# 612_jetracer_esp32s3_030011.net
KiCad netlist of a schematic drawn in EAGLE
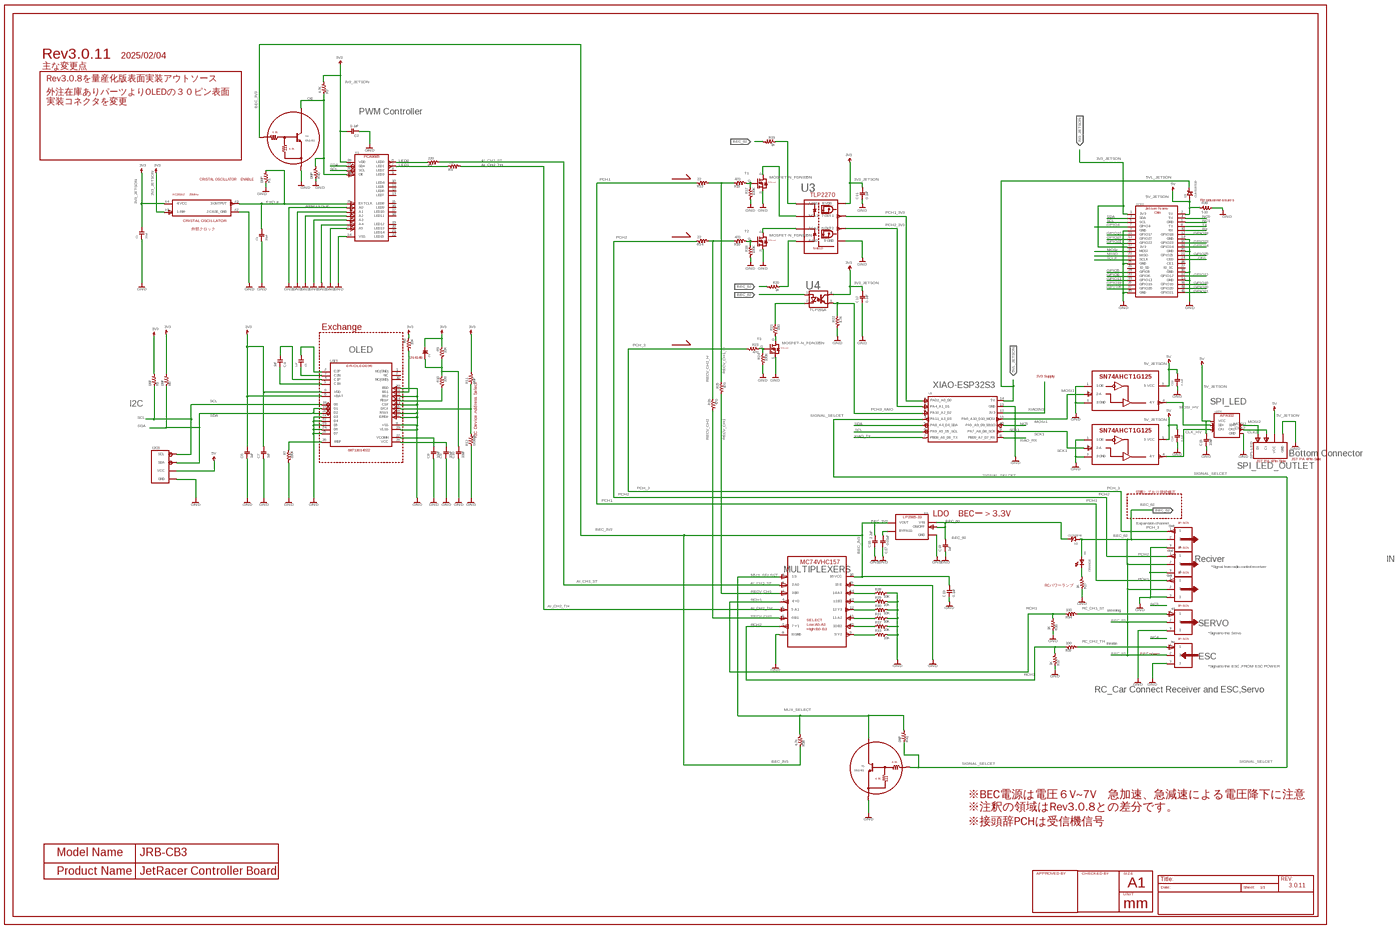
[diagram p0: schematic, sheet 1, overview]
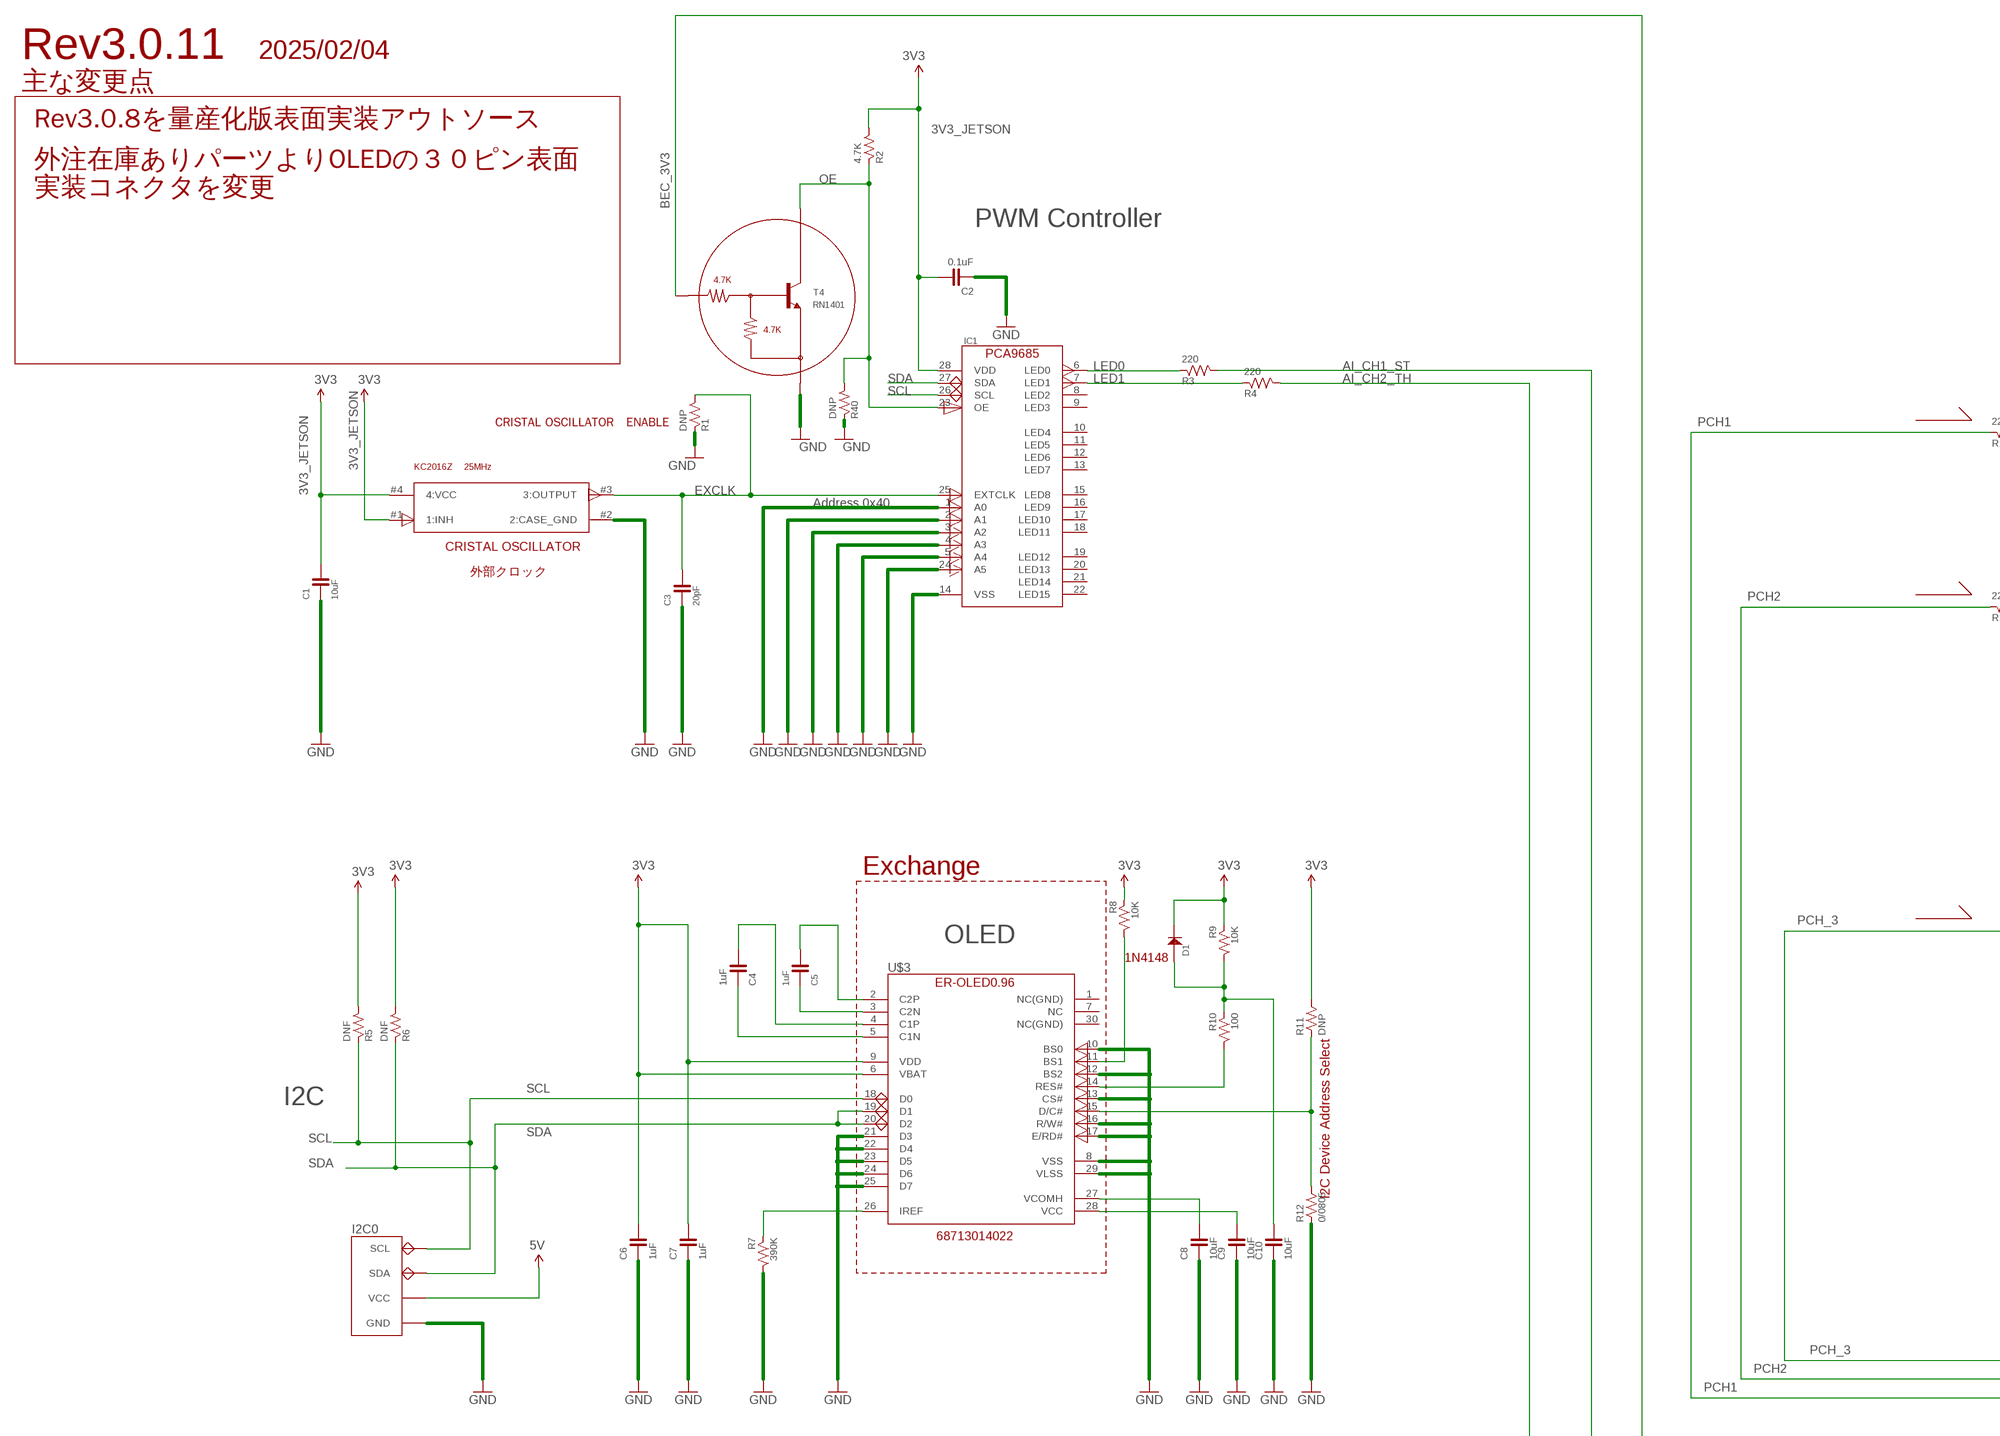
[diagram p1: schematic, sheet 1, part 1 of 4]
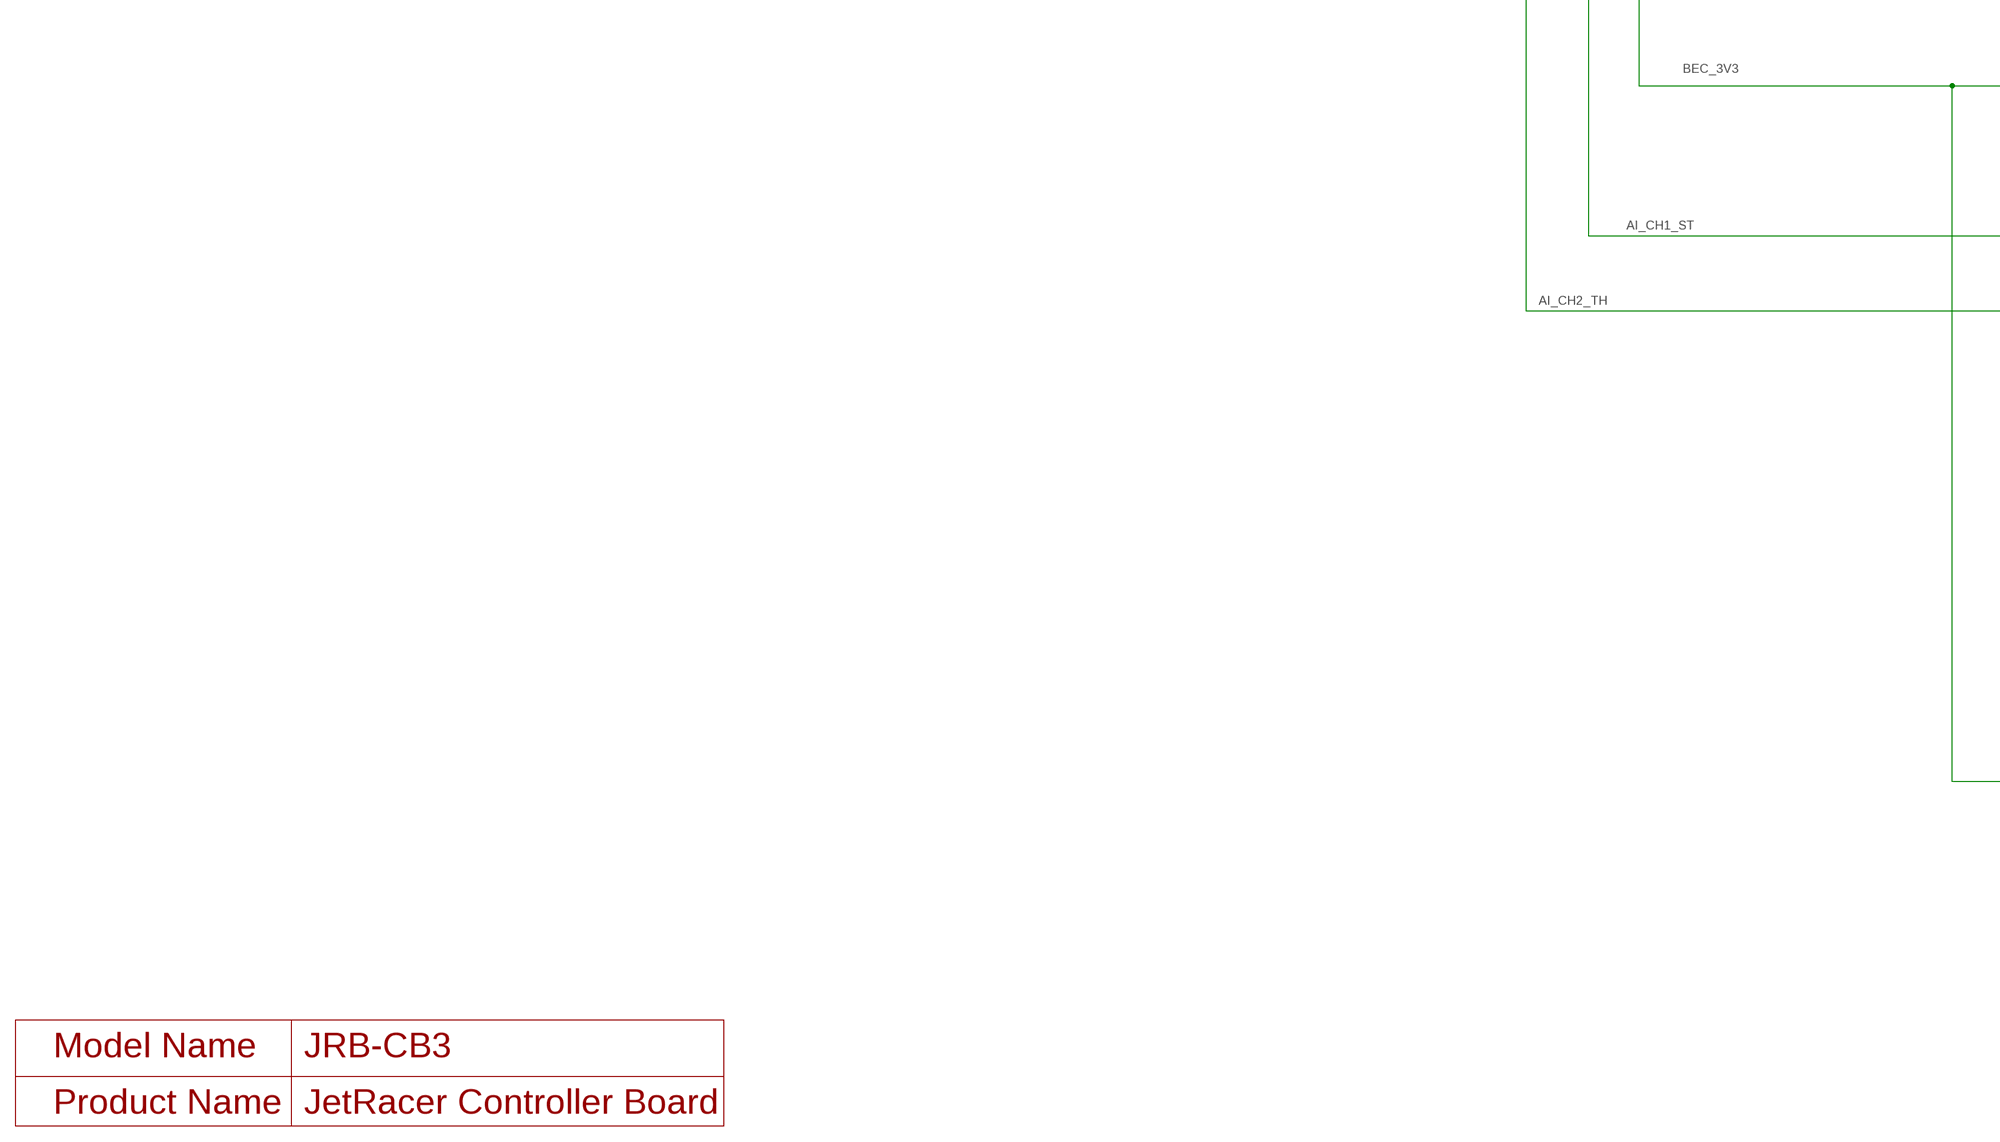
[diagram p2: schematic, sheet 1, part 2 of 4]
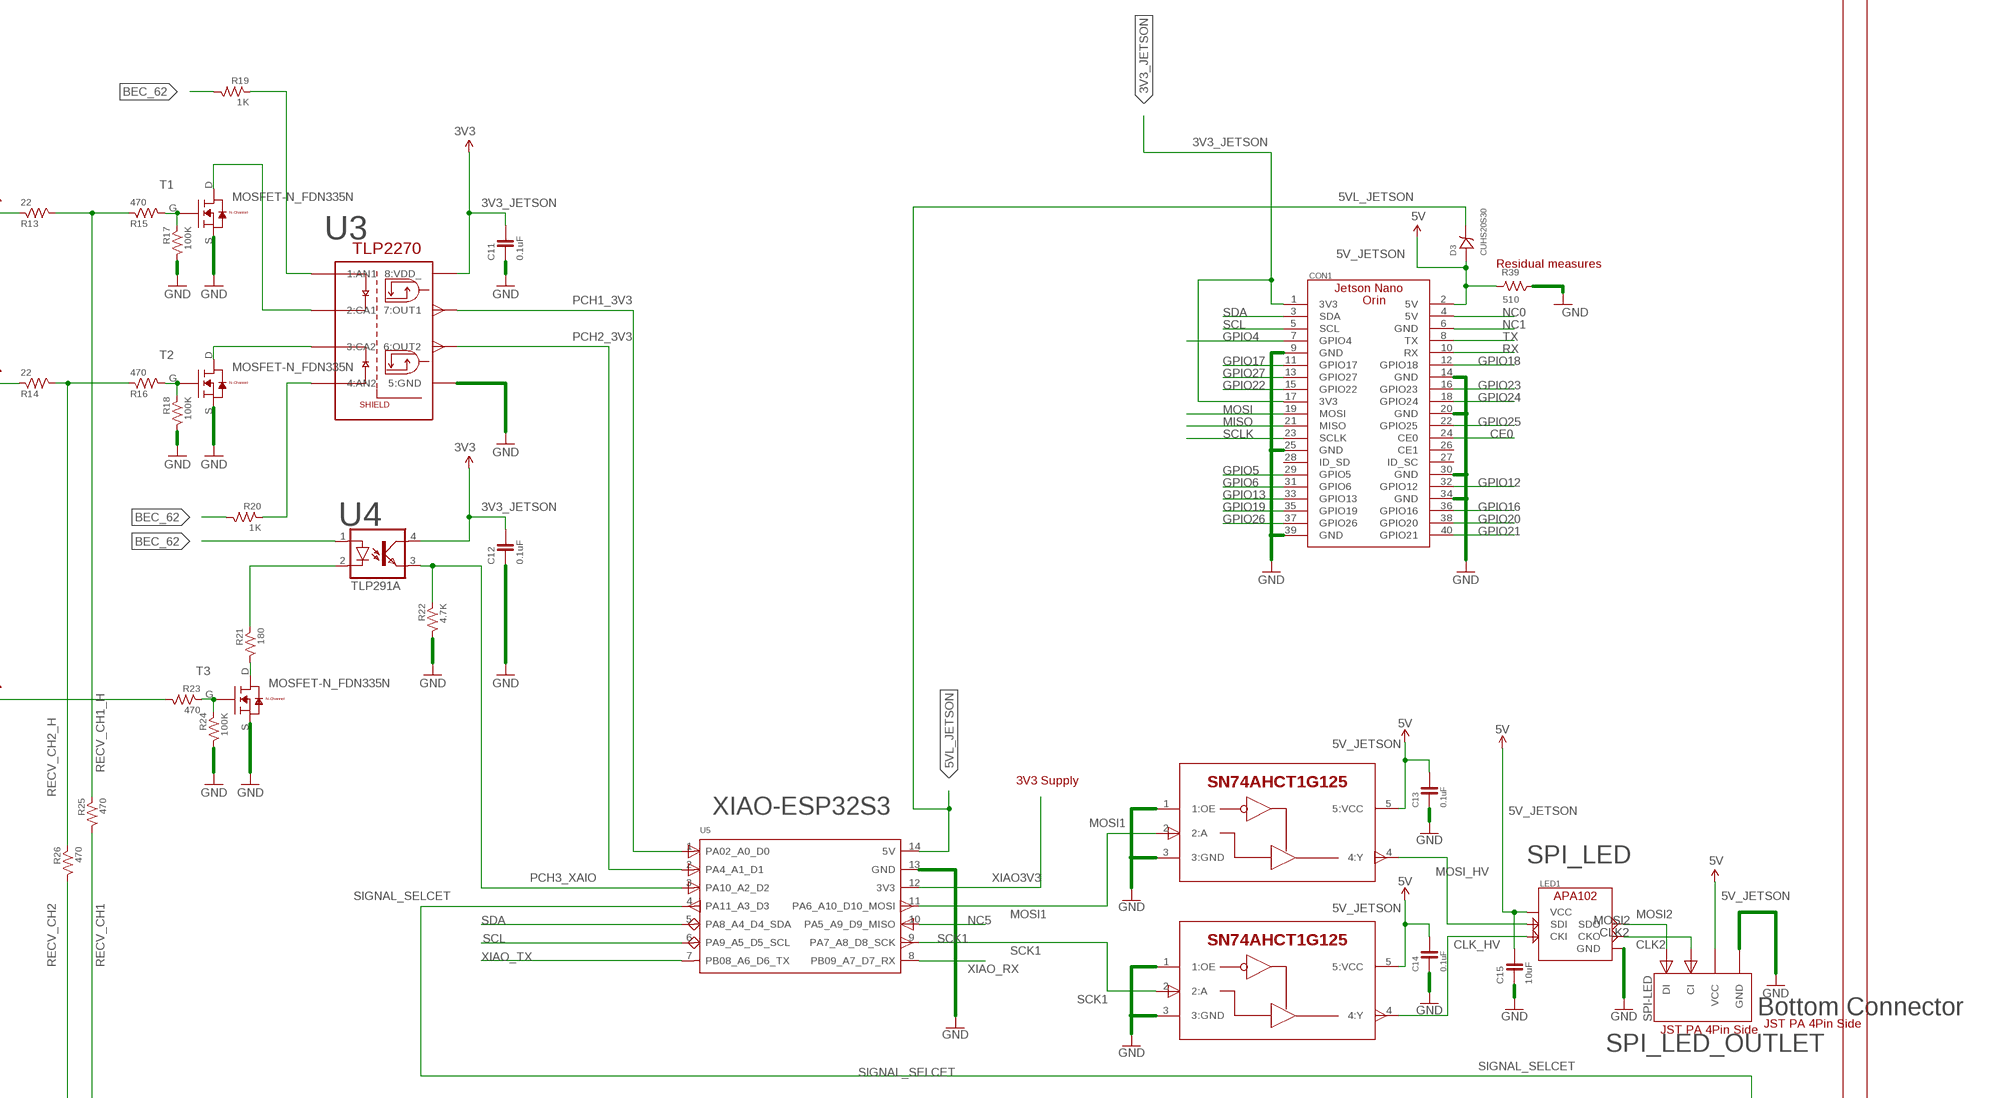
[diagram p3: schematic, sheet 1, part 3 of 4]
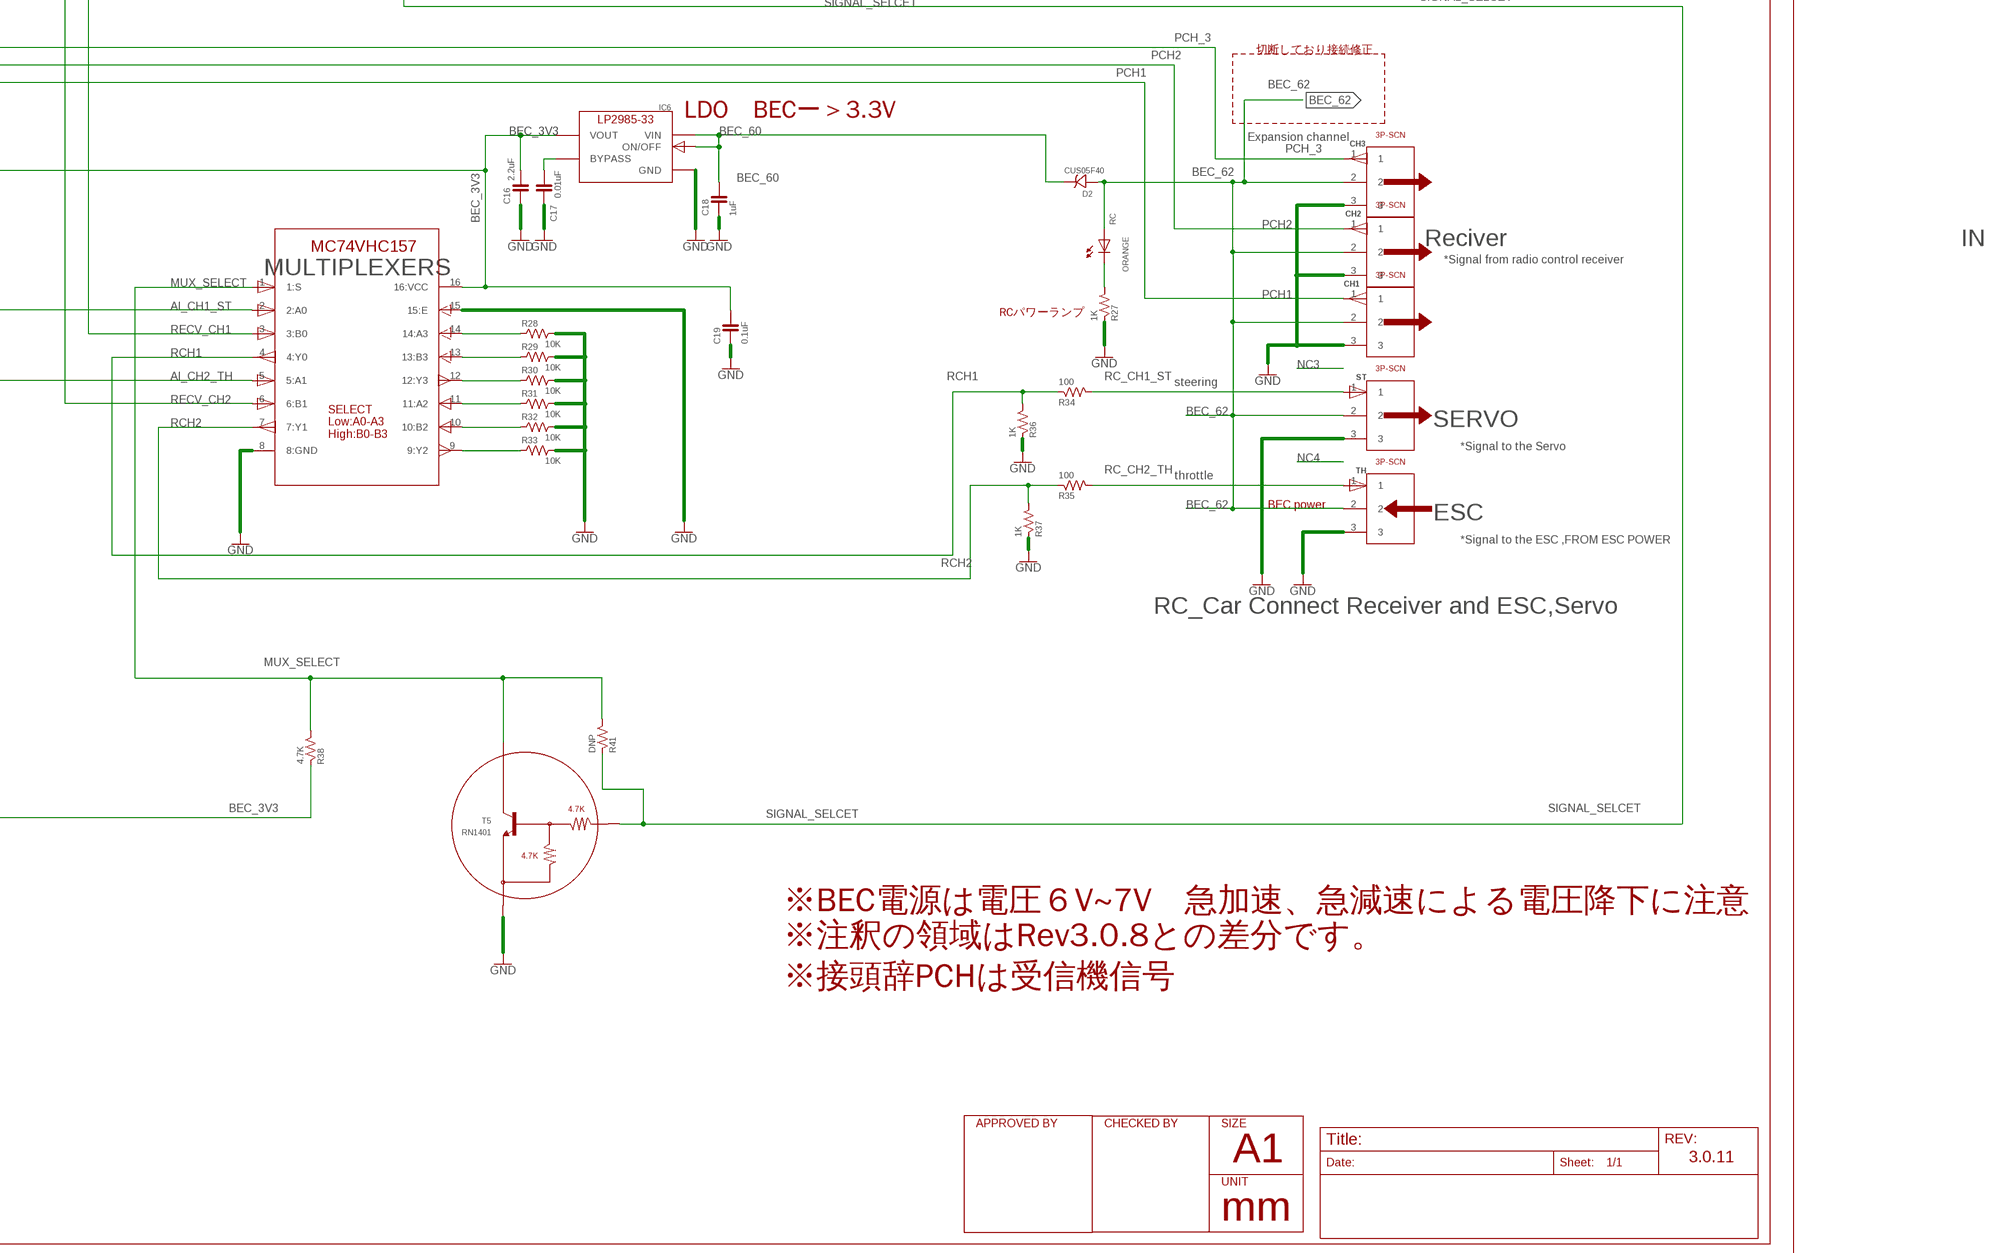
[diagram p4: schematic, sheet 1, part 4 of 4]

(export (version "E")
  (design (tool "Eeschema 10.0.6"))
  (components
    (comp (ref "C1")
      (value "10uF")
      (footprint "eagle-import:0402")
      (libsource (lib "eagle-import") (part "CAPACITOR-0402"))
    )
    (comp (ref "C2")
      (value "0.1uF")
      (footprint "eagle-import:0603")
      (libsource (lib "eagle-import") (part "CAPACITOR-0603"))
    )
    (comp (ref "C3")
      (value "20pF")
      (footprint "eagle-import:0402")
      (libsource (lib "eagle-import") (part "CAPACITOR-0402"))
    )
    (comp (ref "C4")
      (value "1uF")
      (footprint "eagle-import:0603")
      (libsource (lib "eagle-import") (part "CAPACITOR-0603"))
    )
    (comp (ref "C5")
      (value "1uF")
      (footprint "eagle-import:0603")
      (libsource (lib "eagle-import") (part "CAPACITOR-0603"))
    )
    (comp (ref "C6")
      (value "1uF")
      (footprint "eagle-import:0603")
      (libsource (lib "eagle-import") (part "CAPACITOR-0603"))
    )
    (comp (ref "C7")
      (value "1uF")
      (footprint "eagle-import:0603")
      (libsource (lib "eagle-import") (part "CAPACITOR-0603"))
    )
    (comp (ref "C8")
      (value "10uF")
      (footprint "eagle-import:0603")
      (libsource (lib "eagle-import") (part "CAPACITOR-0603"))
    )
    (comp (ref "C9")
      (value "10uF")
      (footprint "eagle-import:0603")
      (libsource (lib "eagle-import") (part "CAPACITOR-0603"))
    )
    (comp (ref "C10")
      (value "10uF")
      (footprint "eagle-import:0603")
      (libsource (lib "eagle-import") (part "CAPACITOR-0603"))
    )
    (comp (ref "C11")
      (value "0.1uF")
      (footprint "eagle-import:0603")
      (libsource (lib "eagle-import") (part "CAPACITOR-0603"))
    )
    (comp (ref "C12")
      (value "0.1uF")
      (footprint "eagle-import:0603")
      (libsource (lib "eagle-import") (part "CAPACITOR-0603"))
    )
    (comp (ref "C13")
      (value "0.1uF")
      (footprint "eagle-import:0402")
      (libsource (lib "eagle-import") (part "CAPACITOR-0402"))
    )
    (comp (ref "C14")
      (value "0.1uF")
      (footprint "eagle-import:0402")
      (libsource (lib "eagle-import") (part "CAPACITOR-0402"))
    )
    (comp (ref "C15")
      (value "10uF")
      (footprint "eagle-import:0603")
      (libsource (lib "eagle-import") (part "CAPACITOR-0603"))
    )
    (comp (ref "C16")
      (value "2.2uF")
      (footprint "eagle-import:0603")
      (libsource (lib "eagle-import") (part "CAPACITOR-0603"))
    )
    (comp (ref "C17")
      (value "0.01uF")
      (footprint "eagle-import:0603")
      (libsource (lib "eagle-import") (part "CAPACITOR-0603"))
    )
    (comp (ref "C18")
      (value "1uF")
      (footprint "eagle-import:0603")
      (libsource (lib "eagle-import") (part "CAPACITOR-0603"))
    )
    (comp (ref "C19")
      (value "0.1uF")
      (footprint "eagle-import:0603")
      (libsource (lib "eagle-import") (part "CAPACITOR-0603"))
    )
    (comp (ref "CH1")
      (value "3P-SCN")
      (footprint "eagle-import:3P-SCN")
      (libsource (lib "eagle-import") (part "3P-SCN"))
    )
    (comp (ref "CH2")
      (value "3P-SCN")
      (footprint "eagle-import:3P-SCN")
      (libsource (lib "eagle-import") (part "3P-SCN"))
    )
    (comp (ref "CH3")
      (value "3P-SCN")
      (footprint "eagle-import:3P-SCN")
      (libsource (lib "eagle-import") (part "3P-SCN"))
    )
    (comp (ref "CON1")
      (value "JETSON_NANOJETSON_ORIN_NANO")
      (footprint "eagle-import:JETSON_ORIN_NANO_DIMENTION")
      (libsource (lib "eagle-import") (part "JETSON_NANOJETSON_ORIN_NANO"))
    )
    (comp (ref "D1")
      (value "1N4148")
      (footprint "eagle-import:1N4148W")
      (libsource (lib "eagle-import") (part "1N4148"))
    )
    (comp (ref "D2")
      (value "CUS05F40")
      (footprint "eagle-import:CUS05F40")
      (libsource (lib "eagle-import") (part "CUS05F40"))
    )
    (comp (ref "D3")
      (value "CUHS20S30")
      (footprint "eagle-import:US2H")
      (libsource (lib "eagle-import") (part "CUHS20S30"))
    )
    (comp (ref "I2C0")
      (value "FABO_BRICK_I2C-B04B-PASK-1")
      (footprint "eagle-import:FABO_BRICK_I2C_B04B-PASK-1")
      (libsource (lib "eagle-import") (part "FABO_BRICK_I2C-B04B-PASK-1"))
    )
    (comp (ref "IC1")
      (value "PCA9685PW,BS")
      (footprint "eagle-import:PCA9685")
      (libsource (lib "eagle-import") (part "PCA9685PW,BS"))
    )
    (comp (ref "IC3")
      (value "SN74AHCT1G125")
      (footprint "eagle-import:SOT-1DOT1")
      (libsource (lib "eagle-import") (part "SN74AHCT1G125"))
    )
    (comp (ref "IC4")
      (value "SN74AHCT1G125")
      (footprint "eagle-import:SOT-1DOT1")
      (libsource (lib "eagle-import") (part "SN74AHCT1G125"))
    )
    (comp (ref "IC5")
      (value "MC74VHC157")
      (footprint "eagle-import:MC74VHC157_TSSOP-16")
      (libsource (lib "eagle-import") (part "MC74VHC157"))
    )
    (comp (ref "IC6")
      (value "LP2985-33DBVR")
      (footprint "eagle-import:SOT-23-5")
      (libsource (lib "eagle-import") (part "LP2985-33DBVR"))
    )
    (comp (ref "LED1")
      (value "APA102_IPIXEL")
      (footprint "eagle-import:APA102_2020")
      (libsource (lib "eagle-import") (part "APA102_IPIXEL"))
    )
    (comp (ref "R1")
      (value "DNP")
      (footprint "eagle-import:0603")
      (libsource (lib "eagle-import") (part "RESISTOR-0603"))
    )
    (comp (ref "R2")
      (value "4.7K")
      (footprint "eagle-import:0603")
      (libsource (lib "eagle-import") (part "RESISTOR-0603"))
    )
    (comp (ref "R3")
      (value "220")
      (footprint "eagle-import:0603")
      (libsource (lib "eagle-import") (part "RESISTOR-0603"))
    )
    (comp (ref "R4")
      (value "220")
      (footprint "eagle-import:0603")
      (libsource (lib "eagle-import") (part "RESISTOR-0603"))
    )
    (comp (ref "R5")
      (value "DNF")
      (footprint "eagle-import:0603")
      (libsource (lib "eagle-import") (part "RESISTOR-0603"))
    )
    (comp (ref "R6")
      (value "DNF")
      (footprint "eagle-import:0603")
      (libsource (lib "eagle-import") (part "RESISTOR-0603"))
    )
    (comp (ref "R7")
      (value "390K")
      (footprint "eagle-import:0603")
      (libsource (lib "eagle-import") (part "RESISTOR-0603"))
    )
    (comp (ref "R8")
      (value "10K")
      (footprint "eagle-import:0603")
      (libsource (lib "eagle-import") (part "RESISTOR-0603"))
    )
    (comp (ref "R9")
      (value "10K")
      (footprint "eagle-import:0603")
      (libsource (lib "eagle-import") (part "RESISTOR-0603"))
    )
    (comp (ref "R10")
      (value "100")
      (footprint "eagle-import:0603")
      (libsource (lib "eagle-import") (part "RESISTOR-0603"))
    )
    (comp (ref "R11")
      (value "DNP")
      (footprint "eagle-import:0805")
      (fields (field (name "SPICEPREFIX") "R"))
      (libsource (lib "eagle-import") (part "RESISTOR-0805"))
    )
    (comp (ref "R12")
      (value "0/0805")
      (footprint "eagle-import:0805")
      (libsource (lib "eagle-import") (part "RESISTOR-0805"))
    )
    (comp (ref "R13")
      (value "22")
      (footprint "eagle-import:0603")
      (libsource (lib "eagle-import") (part "RESISTOR-0603"))
    )
    (comp (ref "R14")
      (value "22")
      (footprint "eagle-import:0603")
      (fields (field (name "SPICEPREFIX") "R"))
      (libsource (lib "eagle-import") (part "RESISTOR-0603"))
    )
    (comp (ref "R15")
      (value "470")
      (footprint "eagle-import:0603")
      (libsource (lib "eagle-import") (part "RESISTOR-0603"))
    )
    (comp (ref "R16")
      (value "470")
      (footprint "eagle-import:0603")
      (libsource (lib "eagle-import") (part "RESISTOR-0603"))
    )
    (comp (ref "R17")
      (value "100K")
      (footprint "eagle-import:0603")
      (libsource (lib "eagle-import") (part "RESISTOR-0603"))
    )
    (comp (ref "R18")
      (value "100K")
      (footprint "eagle-import:0603")
      (libsource (lib "eagle-import") (part "RESISTOR-0603"))
    )
    (comp (ref "R19")
      (value "1K")
      (footprint "eagle-import:0603")
      (libsource (lib "eagle-import") (part "RESISTOR-0603"))
    )
    (comp (ref "R20")
      (value "1K")
      (footprint "eagle-import:0603")
      (libsource (lib "eagle-import") (part "RESISTOR-0603"))
    )
    (comp (ref "R21")
      (value "180")
      (footprint "eagle-import:0603")
      (libsource (lib "eagle-import") (part "RESISTOR-0603"))
    )
    (comp (ref "R22")
      (value "4.7K")
      (footprint "eagle-import:0603")
      (libsource (lib "eagle-import") (part "RESISTOR-0603"))
    )
    (comp (ref "R23")
      (value "470")
      (footprint "eagle-import:0603")
      (libsource (lib "eagle-import") (part "RESISTOR-0603"))
    )
    (comp (ref "R24")
      (value "100K")
      (footprint "eagle-import:0603")
      (libsource (lib "eagle-import") (part "RESISTOR-0603"))
    )
    (comp (ref "R25")
      (value "470")
      (footprint "eagle-import:0603")
      (libsource (lib "eagle-import") (part "RESISTOR-0603"))
    )
    (comp (ref "R26")
      (value "470")
      (footprint "eagle-import:0603")
      (libsource (lib "eagle-import") (part "RESISTOR-0603"))
    )
    (comp (ref "R27")
      (value "1K")
      (footprint "eagle-import:0603")
      (libsource (lib "eagle-import") (part "RESISTOR-0603"))
    )
    (comp (ref "R28")
      (value "10K")
      (footprint "eagle-import:0402")
      (fields (field (name "SPICEPREFIX") "R"))
      (libsource (lib "eagle-import") (part "RESISTOR-0402"))
    )
    (comp (ref "R29")
      (value "10K")
      (footprint "eagle-import:0402")
      (libsource (lib "eagle-import") (part "RESISTOR-0402"))
    )
    (comp (ref "R30")
      (value "10K")
      (footprint "eagle-import:0402")
      (fields (field (name "SPICEPREFIX") "R"))
      (libsource (lib "eagle-import") (part "RESISTOR-0402"))
    )
    (comp (ref "R31")
      (value "10K")
      (footprint "eagle-import:0402")
      (libsource (lib "eagle-import") (part "RESISTOR-0402"))
    )
    (comp (ref "R32")
      (value "10K")
      (footprint "eagle-import:0402")
      (libsource (lib "eagle-import") (part "RESISTOR-0402"))
    )
    (comp (ref "R33")
      (value "10K")
      (footprint "eagle-import:0402")
      (libsource (lib "eagle-import") (part "RESISTOR-0402"))
    )
    (comp (ref "R34")
      (value "100")
      (footprint "eagle-import:0603")
      (libsource (lib "eagle-import") (part "RESISTOR-0603"))
    )
    (comp (ref "R35")
      (value "100")
      (footprint "eagle-import:0603")
      (libsource (lib "eagle-import") (part "RESISTOR-0603"))
    )
    (comp (ref "R36")
      (value "1K")
      (footprint "eagle-import:0603")
      (libsource (lib "eagle-import") (part "RESISTOR-0603"))
    )
    (comp (ref "R37")
      (value "1K")
      (footprint "eagle-import:0603")
      (libsource (lib "eagle-import") (part "RESISTOR-0603"))
    )
    (comp (ref "R38")
      (value "4.7K")
      (footprint "eagle-import:0603")
      (libsource (lib "eagle-import") (part "RESISTOR-0603"))
    )
    (comp (ref "R39")
      (value "510")
      (footprint "eagle-import:0805")
      (libsource (lib "eagle-import") (part "RESISTOR-0805"))
    )
    (comp (ref "R40")
      (value "DNP")
      (footprint "eagle-import:0603")
      (libsource (lib "eagle-import") (part "RESISTOR-0603"))
    )
    (comp (ref "R41")
      (value "DNP")
      (footprint "eagle-import:0603")
      (libsource (lib "eagle-import") (part "RESISTOR-0603"))
    )
    (comp (ref "RC")
      (value "ORANGE")
      (footprint "eagle-import:0603")
      (libsource (lib "eagle-import") (part "LED-0603"))
    )
    (comp (ref "SPI-LED")
      (value "FABO-SPI-LED-B04B")
      (footprint "eagle-import:SPI-B04B-PASK-1")
      (libsource (lib "eagle-import") (part "FABO-SPI-LED-B04B"))
    )
    (comp (ref "ST")
      (value "3P-SCN")
      (footprint "eagle-import:3P-SCN")
      (libsource (lib "eagle-import") (part "3P-SCN"))
    )
    (comp (ref "T1")
      (value "MOSFET-N_FDN335N")
      (footprint "eagle-import:SUPERSOT-3")
      (libsource (lib "eagle-import") (part "MOSFET-N_FDN335N"))
    )
    (comp (ref "T2")
      (value "MOSFET-N_FDN335N")
      (footprint "eagle-import:SUPERSOT-3")
      (libsource (lib "eagle-import") (part "MOSFET-N_FDN335N"))
    )
    (comp (ref "T3")
      (value "MOSFET-N_FDN335N")
      (footprint "eagle-import:SUPERSOT-3")
      (libsource (lib "eagle-import") (part "MOSFET-N_FDN335N"))
    )
    (comp (ref "T4")
      (value "RN1401")
      (footprint "eagle-import:SC-59")
      (libsource (lib "eagle-import") (part "RN1401"))
    )
    (comp (ref "T5")
      (value "RN1401")
      (footprint "eagle-import:SC-59")
      (libsource (lib "eagle-import") (part "RN1401"))
    )
    (comp (ref "TH")
      (value "3P-SCN")
      (footprint "eagle-import:3P-SCN")
      (libsource (lib "eagle-import") (part "3P-SCN"))
    )
    (comp (ref "U$3")
      (value "68713014022(OLED096)")
      (footprint "eagle-import:68713014022")
      (libsource (lib "eagle-import") (part "68713014022(OLED096)"))
    )
    (comp (ref "U1")
      (value "KC2016Z")
      (footprint "eagle-import:KC2016Z")
      (fields (field (name "SPICEPREFIX") "E"))
      (libsource (lib "eagle-import") (part "KC2016Z"))
    )
    (comp (ref "U3")
      (value "TLP2270")
      (footprint "eagle-import:TLP2270")
      (libsource (lib "eagle-import") (part "TLP2270"))
    )
    (comp (ref "U4")
      (value "TLP291A")
      (footprint "eagle-import:11-3C1")
      (libsource (lib "eagle-import") (part "TLP291A"))
    )
    (comp (ref "U5")
      (value "MOUDLE-SEEEDUINO-XIAO-ESP32C3SINGLESIDE")
      (footprint "eagle-import:MOUDLE14P-DIP_SINGLE")
      (libsource (lib "eagle-import") (part "MOUDLE-SEEEDUINO-XIAO-ESP32C3SINGLESIDE"))
    )
  )
  (nets
    (net (code "1") (name "/AI_CH1_ST") (class "Default")
      (node (ref "IC5") (pin "2") (pinfunction "2:A0_2") (pintype "bidirectional"))
      (node (ref "R3") (pin "2") (pinfunction "2_2") (pintype "bidirectional"))
    )
    (net (code "2") (name "/AI_CH2_TH") (class "Default")
      (node (ref "IC5") (pin "5") (pinfunction "5:A1_5") (pintype "bidirectional"))
      (node (ref "R4") (pin "2") (pinfunction "2_2") (pintype "bidirectional"))
    )
    (net (code "3") (name "/BEC_3V3") (class "Default")
      (node (ref "C16") (pin "2") (pinfunction "2_2") (pintype "passive"))
      (node (ref "C19") (pin "2") (pinfunction "2_2") (pintype "passive"))
      (node (ref "IC5") (pin "16") (pinfunction "16:VCC_16") (pintype "bidirectional"))
      (node (ref "IC6") (pin "5") (pinfunction "VOUT_5") (pintype "output"))
      (node (ref "R38") (pin "1") (pinfunction "1_1") (pintype "bidirectional"))
      (node (ref "T4") (pin "B") (pinfunction "B_B") (pintype "passive"))
    )
    (net (code "4") (name "/BEC_60") (class "Default")
      (node (ref "C18") (pin "2") (pinfunction "2_2") (pintype "passive"))
      (node (ref "D2") (pin "C") (pinfunction "CATHODE_C") (pintype "bidirectional"))
      (node (ref "IC6") (pin "1") (pinfunction "VIN_1") (pintype "input"))
      (node (ref "IC6") (pin "3") (pinfunction "ON/OFF_3") (pintype "input"))
    )
    (net (code "5") (name "/CE0") (class "Default")
      (node (ref "CON1") (pin "24") (pinfunction "CE0_24") (pintype "bidirectional"))
    )
    (net (code "6") (name "/CLK2") (class "Default")
      (node (ref "LED1") (pin "CKO") (pinfunction "CKO_CKO") (pintype "bidirectional"))
      (node (ref "SPI-LED") (pin "CI") (pinfunction "CI_CI") (pintype "bidirectional"))
    )
    (net (code "7") (name "/CLK_HV") (class "Default")
      (node (ref "IC4") (pin "4") (pinfunction "4:Y_4") (pintype "output"))
      (node (ref "LED1") (pin "CKI") (pinfunction "CKI_CKI") (pintype "bidirectional"))
    )
    (net (code "8") (name "/EXCLK") (class "Default")
      (node (ref "C3") (pin "2") (pinfunction "2_2") (pintype "passive"))
      (node (ref "IC1") (pin "25") (pinfunction "EXTCLK_25") (pintype "bidirectional"))
      (node (ref "R1") (pin "2") (pinfunction "2_2") (pintype "bidirectional"))
      (node (ref "U1") (pin "#3") (pinfunction "3:OUTPUT_#3") (pintype "bidirectional"))
    )
    (net (code "9") (name "/GPIO4") (class "Default")
      (node (ref "CON1") (pin "7") (pinfunction "GPIO4_7") (pintype "bidirectional"))
    )
    (net (code "10") (name "/GPIO5") (class "Default")
      (node (ref "CON1") (pin "29") (pinfunction "GPIO5_29") (pintype "bidirectional"))
    )
    (net (code "11") (name "/GPIO6") (class "Default")
      (node (ref "CON1") (pin "31") (pinfunction "GPIO6_31") (pintype "bidirectional"))
    )
    (net (code "12") (name "/GPIO12") (class "Default")
      (node (ref "CON1") (pin "32") (pinfunction "GPIO12_32") (pintype "bidirectional"))
    )
    (net (code "13") (name "/GPIO13") (class "Default")
      (node (ref "CON1") (pin "33") (pinfunction "GPIO13_33") (pintype "bidirectional"))
    )
    (net (code "14") (name "/GPIO16") (class "Default")
      (node (ref "CON1") (pin "36") (pinfunction "GPIO16_36") (pintype "bidirectional"))
    )
    (net (code "15") (name "/GPIO17") (class "Default")
      (node (ref "CON1") (pin "11") (pinfunction "GPIO17_11") (pintype "bidirectional"))
    )
    (net (code "16") (name "/GPIO18") (class "Default")
      (node (ref "CON1") (pin "12") (pinfunction "GPIO18_12") (pintype "bidirectional"))
    )
    (net (code "17") (name "/GPIO19") (class "Default")
      (node (ref "CON1") (pin "35") (pinfunction "GPIO19_35") (pintype "bidirectional"))
    )
    (net (code "18") (name "/GPIO20") (class "Default")
      (node (ref "CON1") (pin "38") (pinfunction "GPIO20_38") (pintype "bidirectional"))
    )
    (net (code "19") (name "/GPIO21") (class "Default")
      (node (ref "CON1") (pin "40") (pinfunction "GPIO21_40") (pintype "bidirectional"))
    )
    (net (code "20") (name "/GPIO22") (class "Default")
      (node (ref "CON1") (pin "15") (pinfunction "GPIO22_15") (pintype "bidirectional"))
    )
    (net (code "21") (name "/GPIO23") (class "Default")
      (node (ref "CON1") (pin "16") (pinfunction "GPIO23_16") (pintype "bidirectional"))
    )
    (net (code "22") (name "/GPIO24") (class "Default")
      (node (ref "CON1") (pin "18") (pinfunction "GPIO24_18") (pintype "bidirectional"))
    )
    (net (code "23") (name "/GPIO25") (class "Default")
      (node (ref "CON1") (pin "22") (pinfunction "GPIO25_22") (pintype "bidirectional"))
    )
    (net (code "24") (name "/GPIO26") (class "Default")
      (node (ref "CON1") (pin "37") (pinfunction "GPIO26_37") (pintype "bidirectional"))
    )
    (net (code "25") (name "/GPIO27") (class "Default")
      (node (ref "CON1") (pin "13") (pinfunction "GPIO27_13") (pintype "bidirectional"))
    )
    (net (code "26") (name "/LED0") (class "Default")
      (node (ref "IC1") (pin "6") (pinfunction "LED0_6") (pintype "bidirectional"))
      (node (ref "R3") (pin "1") (pinfunction "1_1") (pintype "bidirectional"))
    )
    (net (code "27") (name "/LED1") (class "Default")
      (node (ref "IC1") (pin "7") (pinfunction "LED1_7") (pintype "bidirectional"))
      (node (ref "R4") (pin "1") (pinfunction "1_1") (pintype "bidirectional"))
    )
    (net (code "28") (name "/MISO") (class "Default")
      (node (ref "CON1") (pin "21") (pinfunction "MISO_21") (pintype "bidirectional"))
    )
    (net (code "29") (name "/MOSI") (class "Default")
      (node (ref "CON1") (pin "19") (pinfunction "MOSI_19") (pintype "bidirectional"))
    )
    (net (code "30") (name "/MOSI1") (class "Default")
      (node (ref "IC3") (pin "2") (pinfunction "2:A_2") (pintype "input"))
      (node (ref "U5") (pin "11") (pinfunction "PA6_A10_D10_MOSI_11") (pintype "bidirectional"))
    )
    (net (code "31") (name "/MOSI2") (class "Default")
      (node (ref "LED1") (pin "SDO") (pinfunction "SDO_SDO") (pintype "bidirectional"))
      (node (ref "SPI-LED") (pin "DI") (pinfunction "DI_DI") (pintype "bidirectional"))
    )
    (net (code "32") (name "/MOSI_HV") (class "Default")
      (node (ref "IC3") (pin "4") (pinfunction "4:Y_4") (pintype "output"))
      (node (ref "LED1") (pin "SDI") (pinfunction "SDI_SDI") (pintype "bidirectional"))
    )
    (net (code "33") (name "/MUX_SELECT") (class "Default")
      (node (ref "IC5") (pin "1") (pinfunction "1:S_1") (pintype "bidirectional"))
      (node (ref "R38") (pin "2") (pinfunction "2_2") (pintype "bidirectional"))
      (node (ref "R41") (pin "2") (pinfunction "2_2") (pintype "bidirectional"))
      (node (ref "T5") (pin "C") (pinfunction "C_C") (pintype "passive"))
    )
    (net (code "34") (name "/NC0") (class "Default")
      (node (ref "CON1") (pin "4") (pinfunction "5V_4") (pintype "bidirectional"))
    )
    (net (code "35") (name "/NC1") (class "Default")
      (node (ref "CON1") (pin "6") (pinfunction "GND_6") (pintype "bidirectional"))
    )
    (net (code "38") (name "/NC5") (class "Default")
      (node (ref "U5") (pin "10") (pinfunction "PA5_A9_D9_MISO_10") (pintype "bidirectional"))
    )
    (net (code "39") (name "/OE") (class "Default")
      (node (ref "IC1") (pin "23") (pinfunction "OE_23") (pintype "bidirectional"))
      (node (ref "R2") (pin "1") (pinfunction "1_1") (pintype "bidirectional"))
      (node (ref "R40") (pin "2") (pinfunction "2_2") (pintype "bidirectional"))
      (node (ref "T4") (pin "C") (pinfunction "C_C") (pintype "passive"))
    )
    (net (code "40") (name "/PCH1") (class "Default")
      (node (ref "CH1") (pin "1") (pinfunction "1_1") (pintype "bidirectional"))
      (node (ref "R13") (pin "1") (pinfunction "1_1") (pintype "bidirectional"))
    )
    (net (code "41") (name "/PCH1_3V3") (class "Default")
      (node (ref "U3") (pin "7") (pinfunction "7:OUT1_7") (pintype "bidirectional"))
      (node (ref "U5") (pin "1") (pinfunction "PA02_A0_D0_1") (pintype "bidirectional"))
    )
    (net (code "42") (name "/PCH2") (class "Default")
      (node (ref "CH2") (pin "1") (pinfunction "1_1") (pintype "bidirectional"))
      (node (ref "R14") (pin "1") (pinfunction "1_1") (pintype "bidirectional"))
    )
    (net (code "43") (name "/PCH2_3V3") (class "Default")
      (node (ref "U3") (pin "6") (pinfunction "6:OUT2_6") (pintype "bidirectional"))
      (node (ref "U5") (pin "2") (pinfunction "PA4_A1_D1_2") (pintype "bidirectional"))
    )
    (net (code "44") (name "/PCH3_XAIO") (class "Default")
      (node (ref "R22") (pin "1") (pinfunction "1_1") (pintype "bidirectional"))
      (node (ref "U4") (pin "3") (pinfunction "EMI_3") (pintype "passive"))
      (node (ref "U5") (pin "3") (pinfunction "PA10_A2_D2_3") (pintype "bidirectional"))
    )
    (net (code "45") (name "/PCH_3") (class "Default")
      (node (ref "CH3") (pin "1") (pinfunction "1_1") (pintype "bidirectional"))
      (node (ref "R23") (pin "2") (pinfunction "2_2") (pintype "bidirectional"))
    )
    (net (code "46") (name "/RCH1") (class "Default")
      (node (ref "IC5") (pin "4") (pinfunction "4:Y0_4") (pintype "bidirectional"))
      (node (ref "R34") (pin "1") (pinfunction "1_1") (pintype "bidirectional"))
      (node (ref "R36") (pin "2") (pinfunction "2_2") (pintype "bidirectional"))
    )
    (net (code "47") (name "/RCH2") (class "Default")
      (node (ref "IC5") (pin "7") (pinfunction "7:Y1_7") (pintype "bidirectional"))
      (node (ref "R35") (pin "1") (pinfunction "1_1") (pintype "bidirectional"))
      (node (ref "R37") (pin "2") (pinfunction "2_2") (pintype "bidirectional"))
    )
    (net (code "48") (name "/RC_CH1_ST") (class "Default")
      (node (ref "R34") (pin "2") (pinfunction "2_2") (pintype "bidirectional"))
      (node (ref "ST") (pin "1") (pinfunction "1_1") (pintype "bidirectional"))
    )
    (net (code "49") (name "/RC_CH2_TH") (class "Default")
      (node (ref "R35") (pin "2") (pinfunction "2_2") (pintype "bidirectional"))
      (node (ref "TH") (pin "1") (pinfunction "1_1") (pintype "bidirectional"))
    )
    (net (code "50") (name "/RECV_CH1") (class "Default")
      (node (ref "IC5") (pin "3") (pinfunction "3:B0_3") (pintype "bidirectional"))
      (node (ref "R25") (pin "2") (pinfunction "2_2") (pintype "bidirectional"))
    )
    (net (code "51") (name "/RECV_CH1_H") (class "Default")
      (node (ref "R13") (pin "2") (pinfunction "2_2") (pintype "bidirectional"))
      (node (ref "R15") (pin "1") (pinfunction "1_1") (pintype "bidirectional"))
      (node (ref "R25") (pin "1") (pinfunction "1_1") (pintype "bidirectional"))
    )
    (net (code "52") (name "/RECV_CH2") (class "Default")
      (node (ref "IC5") (pin "6") (pinfunction "6:B1_6") (pintype "bidirectional"))
      (node (ref "R26") (pin "2") (pinfunction "2_2") (pintype "bidirectional"))
    )
    (net (code "53") (name "/RECV_CH2_H") (class "Default")
      (node (ref "R14") (pin "2") (pinfunction "2_2") (pintype "bidirectional"))
      (node (ref "R16") (pin "1") (pinfunction "1_1") (pintype "bidirectional"))
      (node (ref "R26") (pin "1") (pinfunction "1_1") (pintype "bidirectional"))
    )
    (net (code "54") (name "/RX") (class "Default")
      (node (ref "CON1") (pin "10") (pinfunction "RX_10") (pintype "bidirectional"))
    )
    (net (code "55") (name "/SCK1") (class "Default")
      (node (ref "IC4") (pin "2") (pinfunction "2:A_2") (pintype "input"))
      (node (ref "U5") (pin "9") (pinfunction "PA7_A8_D8_SCK_9") (pintype "bidirectional"))
    )
    (net (code "56") (name "/SCL") (class "Default")
      (node (ref "CON1") (pin "5") (pinfunction "SCL_5") (pintype "bidirectional"))
      (node (ref "I2C0") (pin "SCL") (pinfunction "SCL_SCL") (pintype "bidirectional"))
      (node (ref "IC1") (pin "26") (pinfunction "SCL_26") (pintype "bidirectional"))
      (node (ref "R5") (pin "1") (pinfunction "1_1") (pintype "bidirectional"))
      (node (ref "U$3") (pin "18") (pinfunction "D0_18") (pintype "bidirectional"))
      (node (ref "U5") (pin "6") (pinfunction "PA9_A5_D5_SCL_6") (pintype "bidirectional"))
    )
    (net (code "57") (name "/SCLK") (class "Default")
      (node (ref "CON1") (pin "23") (pinfunction "SCLK_23") (pintype "bidirectional"))
    )
    (net (code "58") (name "/SDA") (class "Default")
      (node (ref "CON1") (pin "3") (pinfunction "SDA_3") (pintype "bidirectional"))
      (node (ref "I2C0") (pin "SDA") (pinfunction "SDA_SDA") (pintype "bidirectional"))
      (node (ref "IC1") (pin "27") (pinfunction "SDA_27") (pintype "bidirectional"))
      (node (ref "R6") (pin "1") (pinfunction "1_1") (pintype "bidirectional"))
      (node (ref "U$3") (pin "19") (pinfunction "D1_19") (pintype "bidirectional"))
      (node (ref "U$3") (pin "20") (pinfunction "D2_20") (pintype "bidirectional"))
      (node (ref "U5") (pin "5") (pinfunction "PA8_A4_D4_SDA_5") (pintype "bidirectional"))
    )
    (net (code "59") (name "/SIGNAL_SELCET") (class "Default")
      (node (ref "R41") (pin "1") (pinfunction "1_1") (pintype "bidirectional"))
      (node (ref "T5") (pin "B") (pinfunction "B_B") (pintype "passive"))
      (node (ref "U5") (pin "4") (pinfunction "PA11_A3_D3_4") (pintype "bidirectional"))
    )
    (net (code "60") (name "/TX") (class "Default")
      (node (ref "CON1") (pin "8") (pinfunction "TX_8") (pintype "bidirectional"))
    )
    (net (code "61") (name "/XIAO3V3") (class "Default")
      (node (ref "U5") (pin "12") (pinfunction "3V3_12") (pintype "bidirectional"))
    )
    (net (code "62") (name "/XIAO_RX") (class "Default")
      (node (ref "U5") (pin "8") (pinfunction "PB09_A7_D7_RX_8") (pintype "bidirectional"))
    )
    (net (code "63") (name "/XIAO_TX") (class "Default")
      (node (ref "U5") (pin "7") (pinfunction "PB08_A6_D6_TX_7") (pintype "bidirectional"))
    )
    (net (code "64") (name "3V3_JETSON") (class "Default")
      (node (ref "C1") (pin "2") (pinfunction "2_2") (pintype "passive"))
      (node (ref "C11") (pin "2") (pinfunction "2_2") (pintype "passive"))
      (node (ref "C12") (pin "2") (pinfunction "2_2") (pintype "passive"))
      (node (ref "C2") (pin "2") (pinfunction "2_2") (pintype "passive"))
      (node (ref "C6") (pin "2") (pinfunction "2_2") (pintype "passive"))
      (node (ref "C7") (pin "2") (pinfunction "2_2") (pintype "passive"))
      (node (ref "CON1") (pin "1") (pinfunction "3V3_1") (pintype "bidirectional"))
      (node (ref "CON1") (pin "17") (pinfunction "3V3_17") (pintype "bidirectional"))
      (node (ref "D1") (pin "CATHODE") (pinfunction "CATHODE_CATHODE") (pintype "bidirectional"))
      (node (ref "IC1") (pin "28") (pinfunction "VDD_28") (pintype "bidirectional"))
      (node (ref "R11") (pin "2") (pinfunction "2_2") (pintype "bidirectional"))
      (node (ref "R2") (pin "2") (pinfunction "2_2") (pintype "bidirectional"))
      (node (ref "R5") (pin "2") (pinfunction "2_2") (pintype "bidirectional"))
      (node (ref "R6") (pin "2") (pinfunction "2_2") (pintype "bidirectional"))
      (node (ref "R8") (pin "1") (pinfunction "1_1") (pintype "bidirectional"))
      (node (ref "R9") (pin "1") (pinfunction "1_1") (pintype "bidirectional"))
      (node (ref "U$3") (pin "6") (pinfunction "VBAT_6") (pintype "power_in"))
      (node (ref "U$3") (pin "9") (pinfunction "VDD_9") (pintype "power_in"))
      (node (ref "U1") (pin "#1") (pinfunction "1:INH_#1") (pintype "bidirectional"))
      (node (ref "U1") (pin "#4") (pinfunction "4:VCC_#4") (pintype "bidirectional"))
      (node (ref "U3") (pin "8") (pinfunction "8:VDD__8") (pintype "bidirectional"))
      (node (ref "U4") (pin "4") (pinfunction "COL_4") (pintype "passive"))
    )
    (net (code "65") (name "5V") (class "Default")
      (node (ref "C13") (pin "2") (pinfunction "2_2") (pintype "passive"))
      (node (ref "C14") (pin "2") (pinfunction "2_2") (pintype "passive"))
      (node (ref "C15") (pin "2") (pinfunction "2_2") (pintype "passive"))
      (node (ref "CON1") (pin "2") (pinfunction "5V_2") (pintype "bidirectional"))
      (node (ref "D3") (pin "A") (pinfunction "ANODE_A") (pintype "passive"))
      (node (ref "I2C0") (pin "VCC") (pinfunction "VCC_VCC") (pintype "bidirectional"))
      (node (ref "IC3") (pin "5") (pinfunction "5:VCC_5") (pintype "power_in"))
      (node (ref "IC4") (pin "5") (pinfunction "5:VCC_5") (pintype "power_in"))
      (node (ref "LED1") (pin "VCC") (pinfunction "VCC_VCC") (pintype "bidirectional"))
      (node (ref "R39") (pin "2") (pinfunction "2_2") (pintype "bidirectional"))
      (node (ref "SPI-LED") (pin "VCC") (pinfunction "VCC_VCC") (pintype "bidirectional"))
    )
    (net (code "66") (name "5VL_JETSON") (class "Default")
      (node (ref "D3") (pin "K") (pinfunction "CATHODE_K") (pintype "passive"))
      (node (ref "U5") (pin "14") (pinfunction "5V_14") (pintype "bidirectional"))
    )
    (net (code "67") (name "BEC_62") (class "Default")
      (node (ref "CH1") (pin "2") (pinfunction "2_2") (pintype "power_in"))
      (node (ref "CH2") (pin "2") (pinfunction "2_2") (pintype "power_in"))
      (node (ref "CH3") (pin "2") (pinfunction "2_2") (pintype "power_in"))
      (node (ref "D2") (pin "A") (pinfunction "ANODE_A") (pintype "bidirectional"))
      (node (ref "R19") (pin "2") (pinfunction "2_2") (pintype "bidirectional"))
      (node (ref "R20") (pin "2") (pinfunction "2_2") (pintype "bidirectional"))
      (node (ref "RC") (pin "ANODE") (pinfunction "ANODE_ANODE") (pintype "passive"))
      (node (ref "ST") (pin "2") (pinfunction "2_2") (pintype "power_in"))
      (node (ref "TH") (pin "2") (pinfunction "2_2") (pintype "power_in"))
      (node (ref "U4") (pin "1") (pinfunction "A_1") (pintype "passive"))
    )
    (net (code "68") (name "GND") (class "Default")
      (node (ref "C1") (pin "1") (pinfunction "1_1") (pintype "passive"))
      (node (ref "C10") (pin "1") (pinfunction "1_1") (pintype "passive"))
      (node (ref "C11") (pin "1") (pinfunction "1_1") (pintype "passive"))
      (node (ref "C12") (pin "1") (pinfunction "1_1") (pintype "passive"))
      (node (ref "C13") (pin "1") (pinfunction "1_1") (pintype "passive"))
      (node (ref "C14") (pin "1") (pinfunction "1_1") (pintype "passive"))
      (node (ref "C15") (pin "1") (pinfunction "1_1") (pintype "passive"))
      (node (ref "C16") (pin "1") (pinfunction "1_1") (pintype "passive"))
      (node (ref "C17") (pin "1") (pinfunction "1_1") (pintype "passive"))
      (node (ref "C18") (pin "1") (pinfunction "1_1") (pintype "passive"))
      (node (ref "C19") (pin "1") (pinfunction "1_1") (pintype "passive"))
      (node (ref "C2") (pin "1") (pinfunction "1_1") (pintype "passive"))
      (node (ref "C3") (pin "1") (pinfunction "1_1") (pintype "passive"))
      (node (ref "C6") (pin "1") (pinfunction "1_1") (pintype "passive"))
      (node (ref "C7") (pin "1") (pinfunction "1_1") (pintype "passive"))
      (node (ref "C8") (pin "1") (pinfunction "1_1") (pintype "passive"))
      (node (ref "C9") (pin "1") (pinfunction "1_1") (pintype "passive"))
      (node (ref "CH1") (pin "3") (pinfunction "3_3") (pintype "power_in"))
      (node (ref "CH2") (pin "3") (pinfunction "3_3") (pintype "power_in"))
      (node (ref "CH3") (pin "3") (pinfunction "3_3") (pintype "power_in"))
      (node (ref "CON1") (pin "14") (pinfunction "GND_14") (pintype "bidirectional"))
      (node (ref "CON1") (pin "20") (pinfunction "GND_20") (pintype "bidirectional"))
      (node (ref "CON1") (pin "25") (pinfunction "GND_25") (pintype "bidirectional"))
      (node (ref "CON1") (pin "30") (pinfunction "GND_30") (pintype "bidirectional"))
      (node (ref "CON1") (pin "34") (pinfunction "GND_34") (pintype "bidirectional"))
      (node (ref "CON1") (pin "39") (pinfunction "GND_39") (pintype "bidirectional"))
      (node (ref "CON1") (pin "9") (pinfunction "GND_9") (pintype "bidirectional"))
      (node (ref "I2C0") (pin "GND") (pinfunction "GND_GND") (pintype "bidirectional"))
      (node (ref "IC1") (pin "1") (pinfunction "A0_1") (pintype "bidirectional"))
      (node (ref "IC1") (pin "14") (pinfunction "VSS_14") (pintype "bidirectional"))
      (node (ref "IC1") (pin "2") (pinfunction "A1_2") (pintype "bidirectional"))
      (node (ref "IC1") (pin "24") (pinfunction "A5_24") (pintype "bidirectional"))
      (node (ref "IC1") (pin "3") (pinfunction "A2_3") (pintype "bidirectional"))
      (node (ref "IC1") (pin "4") (pinfunction "A3_4") (pintype "bidirectional"))
      (node (ref "IC1") (pin "5") (pinfunction "A4_5") (pintype "bidirectional"))
      (node (ref "IC3") (pin "1") (pinfunction "1:OE_1") (pintype "input"))
      (node (ref "IC3") (pin "3") (pinfunction "3:GND_3") (pintype "power_in"))
      (node (ref "IC4") (pin "1") (pinfunction "1:OE_1") (pintype "input"))
      (node (ref "IC4") (pin "3") (pinfunction "3:GND_3") (pintype "power_in"))
      (node (ref "IC5") (pin "15") (pinfunction "15:E_15") (pintype "bidirectional"))
      (node (ref "IC5") (pin "8") (pinfunction "8:GND_8") (pintype "bidirectional"))
      (node (ref "IC6") (pin "2") (pinfunction "GND_2") (pintype "power_in"))
      (node (ref "LED1") (pin "GND") (pinfunction "GND_GND") (pintype "bidirectional"))
      (node (ref "R1") (pin "1") (pinfunction "1_1") (pintype "bidirectional"))
      (node (ref "R12") (pin "1") (pinfunction "1_1") (pintype "bidirectional"))
      (node (ref "R17") (pin "2") (pinfunction "2_2") (pintype "bidirectional"))
      (node (ref "R18") (pin "2") (pinfunction "2_2") (pintype "bidirectional"))
      (node (ref "R22") (pin "2") (pinfunction "2_2") (pintype "bidirectional"))
      (node (ref "R24") (pin "2") (pinfunction "2_2") (pintype "bidirectional"))
      (node (ref "R27") (pin "1") (pinfunction "1_1") (pintype "bidirectional"))
      (node (ref "R28") (pin "2") (pinfunction "2_2") (pintype "bidirectional"))
      (node (ref "R29") (pin "2") (pinfunction "2_2") (pintype "bidirectional"))
      (node (ref "R30") (pin "2") (pinfunction "2_2") (pintype "bidirectional"))
      (node (ref "R31") (pin "2") (pinfunction "2_2") (pintype "bidirectional"))
      (node (ref "R32") (pin "2") (pinfunction "2_2") (pintype "bidirectional"))
      (node (ref "R33") (pin "2") (pinfunction "2_2") (pintype "bidirectional"))
      (node (ref "R36") (pin "1") (pinfunction "1_1") (pintype "bidirectional"))
      (node (ref "R37") (pin "1") (pinfunction "1_1") (pintype "bidirectional"))
      (node (ref "R39") (pin "1") (pinfunction "1_1") (pintype "bidirectional"))
      (node (ref "R40") (pin "1") (pinfunction "1_1") (pintype "bidirectional"))
      (node (ref "R7") (pin "2") (pinfunction "2_2") (pintype "bidirectional"))
      (node (ref "SPI-LED") (pin "GND") (pinfunction "GND_GND") (pintype "bidirectional"))
      (node (ref "ST") (pin "3") (pinfunction "3_3") (pintype "power_in"))
      (node (ref "T1") (pin "S") (pinfunction "S_S") (pintype "passive"))
      (node (ref "T2") (pin "S") (pinfunction "S_S") (pintype "passive"))
      (node (ref "T3") (pin "S") (pinfunction "S_S") (pintype "passive"))
      (node (ref "T4") (pin "E") (pinfunction "E_E") (pintype "passive"))
      (node (ref "T5") (pin "E") (pinfunction "E_E") (pintype "passive"))
      (node (ref "TH") (pin "3") (pinfunction "3_3") (pintype "power_in"))
      (node (ref "U$3") (pin "10") (pinfunction "BS0_10") (pintype "input"))
      (node (ref "U$3") (pin "12") (pinfunction "BS2_12") (pintype "input"))
      (node (ref "U$3") (pin "13") (pinfunction "CS#_13") (pintype "input"))
      (node (ref "U$3") (pin "16") (pinfunction "R/W#_16") (pintype "input"))
      (node (ref "U$3") (pin "17") (pinfunction "E/RD#_17") (pintype "input"))
      (node (ref "U$3") (pin "21") (pinfunction "D3_21") (pintype "bidirectional"))
      (node (ref "U$3") (pin "22") (pinfunction "D4_22") (pintype "bidirectional"))
      (node (ref "U$3") (pin "23") (pinfunction "D5_23") (pintype "bidirectional"))
      (node (ref "U$3") (pin "24") (pinfunction "D6_24") (pintype "bidirectional"))
      (node (ref "U$3") (pin "25") (pinfunction "D7_25") (pintype "bidirectional"))
      (node (ref "U$3") (pin "29") (pinfunction "VLSS_29") (pintype "power_in"))
      (node (ref "U$3") (pin "8") (pinfunction "VSS_8") (pintype "power_in"))
      (node (ref "U1") (pin "#2") (pinfunction "2:CASE_GND_#2") (pintype "bidirectional"))
      (node (ref "U3") (pin "5") (pinfunction "5:GND_5") (pintype "bidirectional"))
      (node (ref "U5") (pin "13") (pinfunction "GND_13") (pintype "bidirectional"))
    )
    (net (code "69") (name "Net-(C10-Pad2)") (class "Default")
      (node (ref "C10") (pin "2") (pinfunction "2_2") (pintype "passive"))
      (node (ref "D1") (pin "ANODE") (pinfunction "ANODE_ANODE") (pintype "bidirectional"))
      (node (ref "R10") (pin "1") (pinfunction "1_1") (pintype "bidirectional"))
      (node (ref "R9") (pin "2") (pinfunction "2_2") (pintype "bidirectional"))
    )
    (net (code "70") (name "Net-(IC5-9:Y2)") (class "Default")
      (node (ref "IC5") (pin "9") (pinfunction "9:Y2_9") (pintype "bidirectional"))
      (node (ref "R33") (pin "1") (pinfunction "1_1") (pintype "bidirectional"))
    )
    (net (code "71") (name "Net-(IC5-10:B2)") (class "Default")
      (node (ref "IC5") (pin "10") (pinfunction "10:B2_10") (pintype "bidirectional"))
      (node (ref "R32") (pin "1") (pinfunction "1_1") (pintype "bidirectional"))
    )
    (net (code "72") (name "Net-(IC5-11:A2)") (class "Default")
      (node (ref "IC5") (pin "11") (pinfunction "11:A2_11") (pintype "bidirectional"))
      (node (ref "R31") (pin "1") (pinfunction "1_1") (pintype "bidirectional"))
    )
    (net (code "73") (name "Net-(IC5-12:Y3)") (class "Default")
      (node (ref "IC5") (pin "12") (pinfunction "12:Y3_12") (pintype "bidirectional"))
      (node (ref "R30") (pin "1") (pinfunction "1_1") (pintype "bidirectional"))
    )
    (net (code "74") (name "Net-(IC5-13:B3)") (class "Default")
      (node (ref "IC5") (pin "13") (pinfunction "13:B3_13") (pintype "bidirectional"))
      (node (ref "R29") (pin "1") (pinfunction "1_1") (pintype "bidirectional"))
    )
    (net (code "75") (name "Net-(IC5-14:A3)") (class "Default")
      (node (ref "IC5") (pin "14") (pinfunction "14:A3_14") (pintype "bidirectional"))
      (node (ref "R28") (pin "1") (pinfunction "1_1") (pintype "bidirectional"))
    )
    (net (code "76") (name "Net-(IC6-BYPASS)") (class "Default")
      (node (ref "C17") (pin "2") (pinfunction "2_2") (pintype "passive"))
      (node (ref "IC6") (pin "4") (pinfunction "BYPASS_4") (pintype "bidirectional"))
    )
    (net (code "77") (name "Net-(R15-Pad2)") (class "Default")
      (node (ref "R15") (pin "2") (pinfunction "2_2") (pintype "bidirectional"))
      (node (ref "R17") (pin "1") (pinfunction "1_1") (pintype "bidirectional"))
      (node (ref "T1") (pin "G") (pinfunction "G_G") (pintype "passive"))
    )
    (net (code "78") (name "Net-(R16-Pad2)") (class "Default")
      (node (ref "R16") (pin "2") (pinfunction "2_2") (pintype "bidirectional"))
      (node (ref "R18") (pin "1") (pinfunction "1_1") (pintype "bidirectional"))
      (node (ref "T2") (pin "G") (pinfunction "G_G") (pintype "passive"))
    )
    (net (code "79") (name "Net-(R21-Pad2)") (class "Default")
      (node (ref "R21") (pin "2") (pinfunction "2_2") (pintype "bidirectional"))
      (node (ref "T3") (pin "D") (pinfunction "D_D") (pintype "passive"))
    )
    (net (code "80") (name "Net-(R23-Pad1)") (class "Default")
      (node (ref "R23") (pin "1") (pinfunction "1_1") (pintype "bidirectional"))
      (node (ref "R24") (pin "1") (pinfunction "1_1") (pintype "bidirectional"))
      (node (ref "T3") (pin "G") (pinfunction "G_G") (pintype "passive"))
    )
    (net (code "81") (name "Net-(R27-Pad2)") (class "Default")
      (node (ref "R27") (pin "2") (pinfunction "2_2") (pintype "bidirectional"))
      (node (ref "RC") (pin "CATHODE") (pinfunction "CATHODE_CATHODE") (pintype "passive"))
    )
    (net (code "82") (name "Net-(U$3-BS1)") (class "Default")
      (node (ref "R8") (pin "2") (pinfunction "2_2") (pintype "bidirectional"))
      (node (ref "U$3") (pin "11") (pinfunction "BS1_11") (pintype "input"))
    )
    (net (code "83") (name "Net-(U$3-C1N)") (class "Default")
      (node (ref "C4") (pin "1") (pinfunction "1_1") (pintype "passive"))
      (node (ref "U$3") (pin "5") (pinfunction "C1N_5") (pintype "input"))
    )
    (net (code "84") (name "Net-(U$3-C1P)") (class "Default")
      (node (ref "C4") (pin "2") (pinfunction "2_2") (pintype "passive"))
      (node (ref "U$3") (pin "4") (pinfunction "C1P_4") (pintype "input"))
    )
    (net (code "85") (name "Net-(U$3-C2N)") (class "Default")
      (node (ref "C5") (pin "1") (pinfunction "1_1") (pintype "passive"))
      (node (ref "U$3") (pin "3") (pinfunction "C2N_3") (pintype "input"))
    )
    (net (code "86") (name "Net-(U$3-C2P)") (class "Default")
      (node (ref "C5") (pin "2") (pinfunction "2_2") (pintype "passive"))
      (node (ref "U$3") (pin "2") (pinfunction "C2P_2") (pintype "input"))
    )
    (net (code "87") (name "Net-(U$3-D{slash}C#)") (class "Default")
      (node (ref "R11") (pin "1") (pinfunction "1_1") (pintype "bidirectional"))
      (node (ref "R12") (pin "2") (pinfunction "2_2") (pintype "bidirectional"))
      (node (ref "U$3") (pin "15") (pinfunction "D/C#_15") (pintype "input"))
    )
    (net (code "88") (name "Net-(U$3-IREF)") (class "Default")
      (node (ref "R7") (pin "1") (pinfunction "1_1") (pintype "bidirectional"))
      (node (ref "U$3") (pin "26") (pinfunction "IREF_26") (pintype "input"))
    )
    (net (code "89") (name "Net-(U$3-RES#)") (class "Default")
      (node (ref "R10") (pin "2") (pinfunction "2_2") (pintype "bidirectional"))
      (node (ref "U$3") (pin "14") (pinfunction "RES#_14") (pintype "input"))
    )
    (net (code "90") (name "Net-(U$3-VCC)") (class "Default")
      (node (ref "C9") (pin "2") (pinfunction "2_2") (pintype "passive"))
      (node (ref "U$3") (pin "28") (pinfunction "VCC_28") (pintype "power_in"))
    )
    (net (code "91") (name "Net-(U$3-VCOMH)") (class "Default")
      (node (ref "C8") (pin "2") (pinfunction "2_2") (pintype "passive"))
      (node (ref "U$3") (pin "27") (pinfunction "VCOMH_27") (pintype "output"))
    )
    (net (code "92") (name "Net-(U3-1:AN1)") (class "Default")
      (node (ref "R19") (pin "1") (pinfunction "1_1") (pintype "bidirectional"))
      (node (ref "U3") (pin "1") (pinfunction "1:AN1_1") (pintype "bidirectional"))
    )
    (net (code "93") (name "Net-(U3-2:CA1)") (class "Default")
      (node (ref "T1") (pin "D") (pinfunction "D_D") (pintype "passive"))
      (node (ref "U3") (pin "2") (pinfunction "2:CA1_2") (pintype "bidirectional"))
    )
    (net (code "94") (name "Net-(U3-3:CA2)") (class "Default")
      (node (ref "T2") (pin "D") (pinfunction "D_D") (pintype "passive"))
      (node (ref "U3") (pin "3") (pinfunction "3:CA2_3") (pintype "bidirectional"))
    )
    (net (code "95") (name "Net-(U3-4:AN2)") (class "Default")
      (node (ref "R20") (pin "1") (pinfunction "1_1") (pintype "bidirectional"))
      (node (ref "U3") (pin "4") (pinfunction "4:AN2_4") (pintype "bidirectional"))
    )
    (net (code "96") (name "Net-(U4-C)") (class "Default")
      (node (ref "R21") (pin "1") (pinfunction "1_1") (pintype "bidirectional"))
      (node (ref "U4") (pin "2") (pinfunction "C_2") (pintype "passive"))
    )
    (net (code "97") (name "unconnected-(CON1-CE1-Pad26)") (class "Default")
      (node (ref "CON1") (pin "26") (pinfunction "CE1_26") (pintype "bidirectional"))
    )
    (net (code "98") (name "unconnected-(CON1-ID_SC-Pad27)") (class "Default")
      (node (ref "CON1") (pin "27") (pinfunction "ID_SC_27") (pintype "bidirectional"))
    )
    (net (code "99") (name "unconnected-(CON1-ID_SD-Pad28)") (class "Default")
      (node (ref "CON1") (pin "28") (pinfunction "ID_SD_28") (pintype "bidirectional"))
    )
    (net (code "100") (name "unconnected-(IC1-LED2-Pad8)") (class "Default")
      (node (ref "IC1") (pin "8") (pinfunction "LED2_8") (pintype "bidirectional"))
    )
    (net (code "101") (name "unconnected-(IC1-LED3-Pad9)") (class "Default")
      (node (ref "IC1") (pin "9") (pinfunction "LED3_9") (pintype "bidirectional"))
    )
    (net (code "102") (name "unconnected-(IC1-LED4-Pad10)") (class "Default")
      (node (ref "IC1") (pin "10") (pinfunction "LED4_10") (pintype "bidirectional"))
    )
    (net (code "103") (name "unconnected-(IC1-LED5-Pad11)") (class "Default")
      (node (ref "IC1") (pin "11") (pinfunction "LED5_11") (pintype "bidirectional"))
    )
    (net (code "104") (name "unconnected-(IC1-LED6-Pad12)") (class "Default")
      (node (ref "IC1") (pin "12") (pinfunction "LED6_12") (pintype "bidirectional"))
    )
    (net (code "105") (name "unconnected-(IC1-LED7-Pad13)") (class "Default")
      (node (ref "IC1") (pin "13") (pinfunction "LED7_13") (pintype "bidirectional"))
    )
    (net (code "106") (name "unconnected-(IC1-LED8-Pad15)") (class "Default")
      (node (ref "IC1") (pin "15") (pinfunction "LED8_15") (pintype "bidirectional"))
    )
    (net (code "107") (name "unconnected-(IC1-LED9-Pad16)") (class "Default")
      (node (ref "IC1") (pin "16") (pinfunction "LED9_16") (pintype "bidirectional"))
    )
    (net (code "108") (name "unconnected-(IC1-LED10-Pad17)") (class "Default")
      (node (ref "IC1") (pin "17") (pinfunction "LED10_17") (pintype "bidirectional"))
    )
    (net (code "109") (name "unconnected-(IC1-LED11-Pad18)") (class "Default")
      (node (ref "IC1") (pin "18") (pinfunction "LED11_18") (pintype "bidirectional"))
    )
    (net (code "110") (name "unconnected-(IC1-LED12-Pad19)") (class "Default")
      (node (ref "IC1") (pin "19") (pinfunction "LED12_19") (pintype "bidirectional"))
    )
    (net (code "111") (name "unconnected-(IC1-LED13-Pad20)") (class "Default")
      (node (ref "IC1") (pin "20") (pinfunction "LED13_20") (pintype "bidirectional"))
    )
    (net (code "112") (name "unconnected-(IC1-LED14-Pad21)") (class "Default")
      (node (ref "IC1") (pin "21") (pinfunction "LED14_21") (pintype "bidirectional"))
    )
    (net (code "113") (name "unconnected-(IC1-LED15-Pad22)") (class "Default")
      (node (ref "IC1") (pin "22") (pinfunction "LED15_22") (pintype "bidirectional"))
    )
    (net (code "114") (name "unconnected-(U$3-NC(GND)-Pad1)") (class "Default")
      (node (ref "U$3") (pin "1") (pinfunction "NC(GND)_1") (pintype "no_connect"))
    )
    (net (code "115") (name "unconnected-(U$3-NC(GND)-Pad30)") (class "Default")
      (node (ref "U$3") (pin "30") (pinfunction "NC(GND)_30") (pintype "no_connect"))
    )
    (net (code "116") (name "unconnected-(U$3-NC-Pad7)") (class "Default")
      (node (ref "U$3") (pin "7") (pinfunction "NC_7") (pintype "no_connect"))
    )
  )
)
